# KX1_DB.net
KiCad netlist of a schematic drawn in Altium Designer
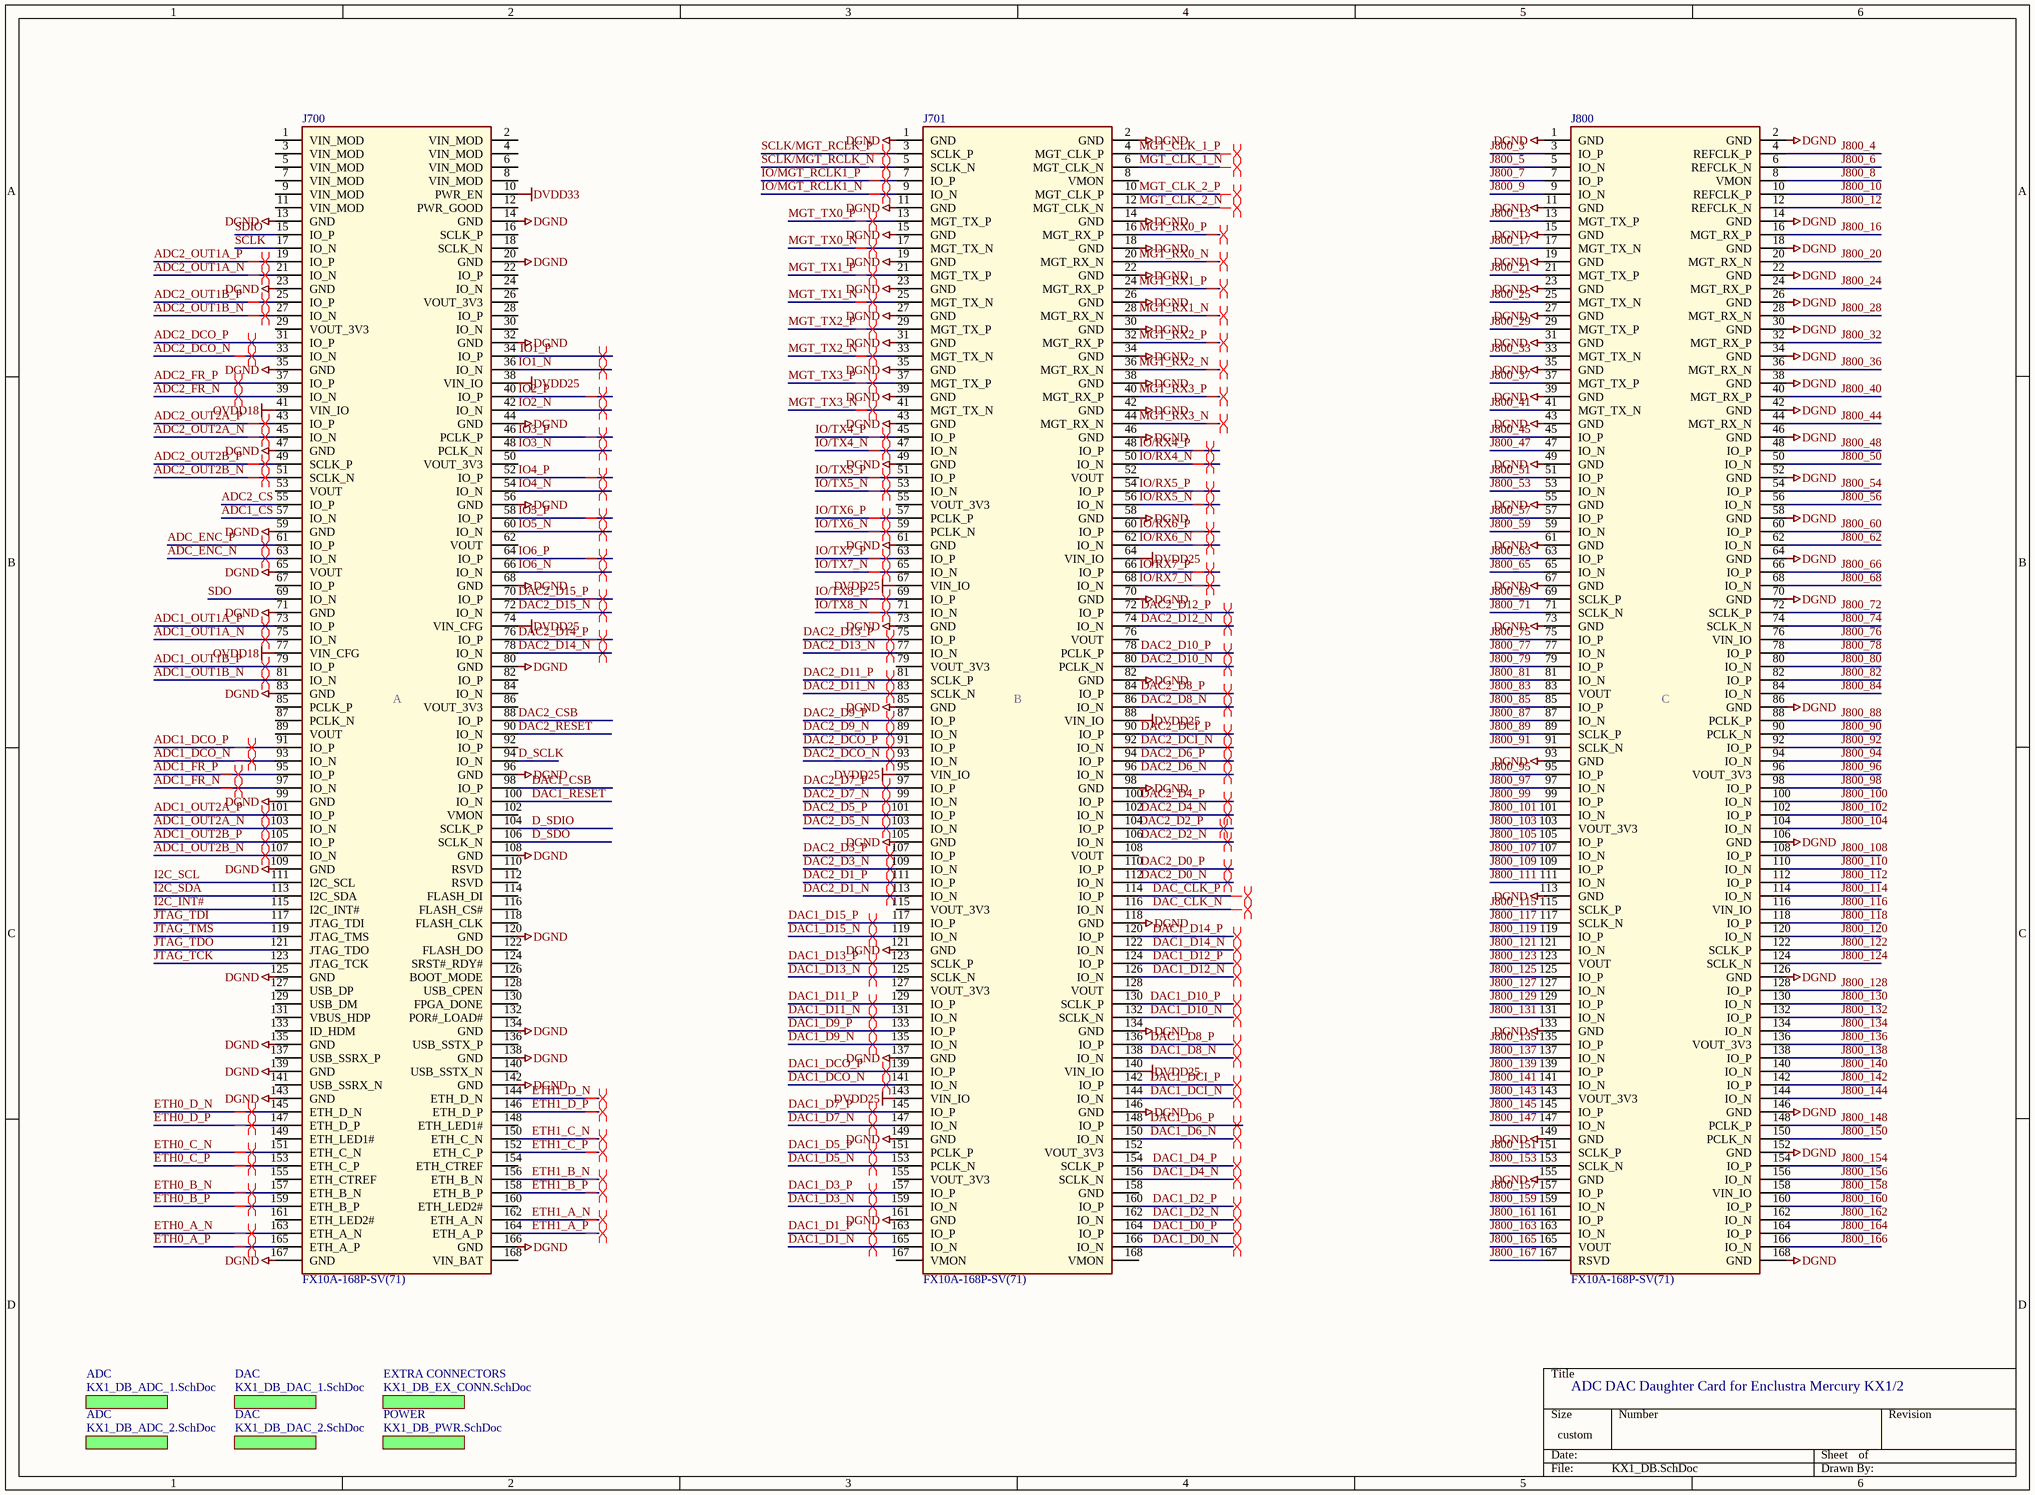
[diagram p0: KX1_DB.SchDoc]

(export (version "E")
  (design (tool "Eeschema 10.0.6"))
  (components
    (comp (ref "J700")
      (value "FX10A-168P-SV(71)")
      (footprint "Mercury_Baseboard_Connector")
      (description "Mercury Baseboard Connector")
      (fields
        (field (name "MANUFACTURER") "Hirose")
        (field (name "DISTPARTNUMBER") "FX10A-168P-SV(71)-ND")
        (field (name "CHECK SCH") "CG_2015-03-03")
      )
      (libsource (lib "Enclustra-Mars-Mercury-Altium-Library") (part "Mercury_Baseboard_Connector-A"))
    )
    (comp (ref "J701")
      (value "FX10A-168P-SV(71)")
      (footprint "Mercury_Baseboard_Connector")
      (description "Mercury Baseboard Connector")
      (fields
        (field (name "MANUFACTURER") "Hirose")
        (field (name "DISTPARTNUMBER") "FX10A-168P-SV(71)-ND")
        (field (name "CHECK SCH") "CG_2015-03-03")
      )
      (libsource (lib "Enclustra-Mars-Mercury-Altium-Library") (part "Mercury_Baseboard_Connector-B"))
    )
    (comp (ref "J800")
      (value "FX10A-168P-SV(71)")
      (footprint "Mercury_Baseboard_Connector")
      (description "Mercury Baseboard Connector")
      (fields
        (field (name "MANUFACTURER") "Hirose")
        (field (name "DISTPARTNUMBER") "FX10A-168P-SV(71)-ND")
        (field (name "CHECK SCH") "CG_2015-03-03")
      )
      (libsource (lib "Enclustra-Mars-Mercury-Altium-Library") (part "Mercury_Baseboard_Connector-C"))
    )
  )
  (nets
    (net (code "1") (name "/ADC1_CS") (class "Default")
      (node (ref "J700") (pin "57") (pinfunction "IO_N_57") (pintype "passive"))
    )
    (net (code "2") (name "/ADC1_DCO_N") (class "Default")
      (node (ref "J700") (pin "93") (pinfunction "IO_N_93") (pintype "passive"))
    )
    (net (code "3") (name "/ADC1_DCO_P") (class "Default")
      (node (ref "J700") (pin "91") (pinfunction "IO_P_91") (pintype "passive"))
    )
    (net (code "4") (name "/ADC1_FR_N") (class "Default")
      (node (ref "J700") (pin "97") (pinfunction "IO_N_97") (pintype "passive"))
    )
    (net (code "5") (name "/ADC1_FR_P") (class "Default")
      (node (ref "J700") (pin "95") (pinfunction "IO_P_95") (pintype "passive"))
    )
    (net (code "6") (name "/ADC1_OUT1A_N") (class "Default")
      (node (ref "J700") (pin "75") (pinfunction "IO_N_75") (pintype "passive"))
    )
    (net (code "7") (name "/ADC1_OUT1A_P") (class "Default")
      (node (ref "J700") (pin "73") (pinfunction "IO_P_73") (pintype "passive"))
    )
    (net (code "8") (name "/ADC1_OUT1B_N") (class "Default")
      (node (ref "J700") (pin "81") (pinfunction "IO_N_81") (pintype "passive"))
    )
    (net (code "9") (name "/ADC1_OUT1B_P") (class "Default")
      (node (ref "J700") (pin "79") (pinfunction "IO_P_79") (pintype "passive"))
    )
    (net (code "10") (name "/ADC1_OUT2A_N") (class "Default")
      (node (ref "J700") (pin "103") (pinfunction "IO_N_103") (pintype "passive"))
    )
    (net (code "11") (name "/ADC1_OUT2A_P") (class "Default")
      (node (ref "J700") (pin "101") (pinfunction "IO_P_101") (pintype "passive"))
    )
    (net (code "12") (name "/ADC1_OUT2B_N") (class "Default")
      (node (ref "J700") (pin "107") (pinfunction "IO_N_107") (pintype "passive"))
    )
    (net (code "13") (name "/ADC1_OUT2B_P") (class "Default")
      (node (ref "J700") (pin "105") (pinfunction "IO_P_105") (pintype "passive"))
    )
    (net (code "14") (name "/ADC2_CS") (class "Default")
      (node (ref "J700") (pin "55") (pinfunction "IO_P_55") (pintype "passive"))
    )
    (net (code "15") (name "/ADC2_DCO_N") (class "Default")
      (node (ref "J700") (pin "33") (pinfunction "IO_N_33") (pintype "passive"))
    )
    (net (code "16") (name "/ADC2_DCO_P") (class "Default")
      (node (ref "J700") (pin "31") (pinfunction "IO_P_31") (pintype "passive"))
    )
    (net (code "17") (name "/ADC2_FR_N") (class "Default")
      (node (ref "J700") (pin "39") (pinfunction "IO_N_39") (pintype "passive"))
    )
    (net (code "18") (name "/ADC2_FR_P") (class "Default")
      (node (ref "J700") (pin "37") (pinfunction "IO_P_37") (pintype "passive"))
    )
    (net (code "19") (name "/ADC2_OUT1A_N") (class "Default")
      (node (ref "J700") (pin "21") (pinfunction "IO_N_21") (pintype "passive"))
    )
    (net (code "20") (name "/ADC2_OUT1A_P") (class "Default")
      (node (ref "J700") (pin "19") (pinfunction "IO_P_19") (pintype "passive"))
    )
    (net (code "21") (name "/ADC2_OUT1B_N") (class "Default")
      (node (ref "J700") (pin "27") (pinfunction "IO_N_27") (pintype "passive"))
    )
    (net (code "22") (name "/ADC2_OUT1B_P") (class "Default")
      (node (ref "J700") (pin "25") (pinfunction "IO_P_25") (pintype "passive"))
    )
    (net (code "23") (name "/ADC2_OUT2A_N") (class "Default")
      (node (ref "J700") (pin "45") (pinfunction "IO_N_45") (pintype "passive"))
    )
    (net (code "24") (name "/ADC2_OUT2A_P") (class "Default")
      (node (ref "J700") (pin "43") (pinfunction "IO_P_43") (pintype "passive"))
    )
    (net (code "25") (name "/ADC2_OUT2B_N") (class "Default")
      (node (ref "J700") (pin "51") (pinfunction "SCLK_N_51") (pintype "passive"))
    )
    (net (code "26") (name "/ADC2_OUT2B_P") (class "Default")
      (node (ref "J700") (pin "49") (pinfunction "SCLK_P_49") (pintype "passive"))
    )
    (net (code "27") (name "/ADC_ENC_N") (class "Default")
      (node (ref "J700") (pin "63") (pinfunction "IO_N_63") (pintype "passive"))
    )
    (net (code "28") (name "/ADC_ENC_P") (class "Default")
      (node (ref "J700") (pin "61") (pinfunction "IO_P_61") (pintype "passive"))
    )
    (net (code "29") (name "/DAC1_CSB") (class "Default")
      (node (ref "J700") (pin "98") (pinfunction "IO_P_98") (pintype "passive"))
    )
    (net (code "30") (name "/DAC1_D0_N") (class "Default")
      (node (ref "J701") (pin "166") (pinfunction "IO_N_166") (pintype "passive"))
    )
    (net (code "31") (name "/DAC1_D0_P") (class "Default")
      (node (ref "J701") (pin "164") (pinfunction "IO_P_164") (pintype "passive"))
    )
    (net (code "32") (name "/DAC1_D1_N") (class "Default")
      (node (ref "J701") (pin "165") (pinfunction "IO_N_165") (pintype "passive"))
    )
    (net (code "33") (name "/DAC1_D1_P") (class "Default")
      (node (ref "J701") (pin "163") (pinfunction "IO_P_163") (pintype "passive"))
    )
    (net (code "34") (name "/DAC1_D2_N") (class "Default")
      (node (ref "J701") (pin "162") (pinfunction "IO_N_162") (pintype "passive"))
    )
    (net (code "35") (name "/DAC1_D2_P") (class "Default")
      (node (ref "J701") (pin "160") (pinfunction "IO_P_160") (pintype "passive"))
    )
    (net (code "36") (name "/DAC1_D3_N") (class "Default")
      (node (ref "J701") (pin "159") (pinfunction "IO_N_159") (pintype "passive"))
    )
    (net (code "37") (name "/DAC1_D3_P") (class "Default")
      (node (ref "J701") (pin "157") (pinfunction "IO_P_157") (pintype "passive"))
    )
    (net (code "38") (name "/DAC1_D4_N") (class "Default")
      (node (ref "J701") (pin "156") (pinfunction "SCLK_N_156") (pintype "passive"))
    )
    (net (code "39") (name "/DAC1_D4_P") (class "Default")
      (node (ref "J701") (pin "154") (pinfunction "SCLK_P_154") (pintype "passive"))
    )
    (net (code "40") (name "/DAC1_D5_N") (class "Default")
      (node (ref "J701") (pin "153") (pinfunction "PCLK_N_153") (pintype "passive"))
    )
    (net (code "41") (name "/DAC1_D5_P") (class "Default")
      (node (ref "J701") (pin "151") (pinfunction "PCLK_P_151") (pintype "passive"))
    )
    (net (code "42") (name "/DAC1_D6_N") (class "Default")
      (node (ref "J701") (pin "150") (pinfunction "IO_N_150") (pintype "passive"))
    )
    (net (code "43") (name "/DAC1_D6_P") (class "Default")
      (node (ref "J701") (pin "148") (pinfunction "IO_P_148") (pintype "passive"))
    )
    (net (code "44") (name "/DAC1_D7_N") (class "Default")
      (node (ref "J701") (pin "147") (pinfunction "IO_N_147") (pintype "passive"))
    )
    (net (code "45") (name "/DAC1_D7_P") (class "Default")
      (node (ref "J701") (pin "145") (pinfunction "IO_P_145") (pintype "passive"))
    )
    (net (code "46") (name "/DAC1_D8_N") (class "Default")
      (node (ref "J701") (pin "138") (pinfunction "IO_N_138") (pintype "passive"))
    )
    (net (code "47") (name "/DAC1_D8_P") (class "Default")
      (node (ref "J701") (pin "136") (pinfunction "IO_P_136") (pintype "passive"))
    )
    (net (code "48") (name "/DAC1_D9_N") (class "Default")
      (node (ref "J701") (pin "135") (pinfunction "IO_N_135") (pintype "passive"))
    )
    (net (code "49") (name "/DAC1_D9_P") (class "Default")
      (node (ref "J701") (pin "133") (pinfunction "IO_P_133") (pintype "passive"))
    )
    (net (code "50") (name "/DAC1_D10_N") (class "Default")
      (node (ref "J701") (pin "132") (pinfunction "SCLK_N_132") (pintype "passive"))
    )
    (net (code "51") (name "/DAC1_D10_P") (class "Default")
      (node (ref "J701") (pin "130") (pinfunction "SCLK_P_130") (pintype "passive"))
    )
    (net (code "52") (name "/DAC1_D11_N") (class "Default")
      (node (ref "J701") (pin "131") (pinfunction "IO_N_131") (pintype "passive"))
    )
    (net (code "53") (name "/DAC1_D11_P") (class "Default")
      (node (ref "J701") (pin "129") (pinfunction "IO_P_129") (pintype "passive"))
    )
    (net (code "54") (name "/DAC1_D12_N") (class "Default")
      (node (ref "J701") (pin "126") (pinfunction "IO_N_126") (pintype "passive"))
    )
    (net (code "55") (name "/DAC1_D12_P") (class "Default")
      (node (ref "J701") (pin "124") (pinfunction "IO_P_124") (pintype "passive"))
    )
    (net (code "56") (name "/DAC1_D13_N") (class "Default")
      (node (ref "J701") (pin "125") (pinfunction "SCLK_N_125") (pintype "passive"))
    )
    (net (code "57") (name "/DAC1_D13_P") (class "Default")
      (node (ref "J701") (pin "123") (pinfunction "SCLK_P_123") (pintype "passive"))
    )
    (net (code "58") (name "/DAC1_D14_N") (class "Default")
      (node (ref "J701") (pin "122") (pinfunction "IO_N_122") (pintype "passive"))
    )
    (net (code "59") (name "/DAC1_D14_P") (class "Default")
      (node (ref "J701") (pin "120") (pinfunction "IO_P_120") (pintype "passive"))
    )
    (net (code "60") (name "/DAC1_D15_N") (class "Default")
      (node (ref "J701") (pin "119") (pinfunction "IO_N_119") (pintype "passive"))
    )
    (net (code "61") (name "/DAC1_D15_P") (class "Default")
      (node (ref "J701") (pin "117") (pinfunction "IO_P_117") (pintype "passive"))
    )
    (net (code "62") (name "/DAC1_DCI_N") (class "Default")
      (node (ref "J701") (pin "144") (pinfunction "IO_N_144") (pintype "passive"))
    )
    (net (code "63") (name "/DAC1_DCI_P") (class "Default")
      (node (ref "J701") (pin "142") (pinfunction "IO_P_142") (pintype "passive"))
    )
    (net (code "64") (name "/DAC1_DCO_N") (class "Default")
      (node (ref "J701") (pin "141") (pinfunction "IO_N_141") (pintype "passive"))
    )
    (net (code "65") (name "/DAC1_DCO_P") (class "Default")
      (node (ref "J701") (pin "139") (pinfunction "IO_P_139") (pintype "passive"))
    )
    (net (code "66") (name "/DAC1_RESET") (class "Default")
      (node (ref "J700") (pin "100") (pinfunction "IO_N_100") (pintype "passive"))
    )
    (net (code "67") (name "/DAC2_CSB") (class "Default")
      (node (ref "J700") (pin "88") (pinfunction "IO_P_88") (pintype "passive"))
    )
    (net (code "68") (name "/DAC2_D0_N") (class "Default")
      (node (ref "J701") (pin "112") (pinfunction "IO_N_112") (pintype "passive"))
    )
    (net (code "69") (name "/DAC2_D0_P") (class "Default")
      (node (ref "J701") (pin "110") (pinfunction "IO_P_110") (pintype "passive"))
    )
    (net (code "70") (name "/DAC2_D1_N") (class "Default")
      (node (ref "J701") (pin "113") (pinfunction "IO_N_113") (pintype "passive"))
    )
    (net (code "71") (name "/DAC2_D1_P") (class "Default")
      (node (ref "J701") (pin "111") (pinfunction "IO_P_111") (pintype "passive"))
    )
    (net (code "72") (name "/DAC2_D2_N") (class "Default")
      (node (ref "J701") (pin "106") (pinfunction "IO_N_106") (pintype "passive"))
    )
    (net (code "73") (name "/DAC2_D2_P") (class "Default")
      (node (ref "J701") (pin "104") (pinfunction "IO_P_104") (pintype "passive"))
    )
    (net (code "74") (name "/DAC2_D3_N") (class "Default")
      (node (ref "J701") (pin "109") (pinfunction "IO_N_109") (pintype "passive"))
    )
    (net (code "75") (name "/DAC2_D3_P") (class "Default")
      (node (ref "J701") (pin "107") (pinfunction "IO_P_107") (pintype "passive"))
    )
    (net (code "76") (name "/DAC2_D4_N") (class "Default")
      (node (ref "J701") (pin "102") (pinfunction "IO_N_102") (pintype "passive"))
    )
    (net (code "77") (name "/DAC2_D4_P") (class "Default")
      (node (ref "J701") (pin "100") (pinfunction "IO_P_100") (pintype "passive"))
    )
    (net (code "78") (name "/DAC2_D5_N") (class "Default")
      (node (ref "J701") (pin "103") (pinfunction "IO_N_103") (pintype "passive"))
    )
    (net (code "79") (name "/DAC2_D5_P") (class "Default")
      (node (ref "J701") (pin "101") (pinfunction "IO_P_101") (pintype "passive"))
    )
    (net (code "80") (name "/DAC2_D6_N") (class "Default")
      (node (ref "J701") (pin "96") (pinfunction "IO_N_96") (pintype "passive"))
    )
    (net (code "81") (name "/DAC2_D6_P") (class "Default")
      (node (ref "J701") (pin "94") (pinfunction "IO_P_94") (pintype "passive"))
    )
    (net (code "82") (name "/DAC2_D7_N") (class "Default")
      (node (ref "J701") (pin "99") (pinfunction "IO_N_99") (pintype "passive"))
    )
    (net (code "83") (name "/DAC2_D7_P") (class "Default")
      (node (ref "J701") (pin "97") (pinfunction "IO_P_97") (pintype "passive"))
    )
    (net (code "84") (name "/DAC2_D8_N") (class "Default")
      (node (ref "J701") (pin "86") (pinfunction "IO_N_86") (pintype "passive"))
    )
    (net (code "85") (name "/DAC2_D8_P") (class "Default")
      (node (ref "J701") (pin "84") (pinfunction "IO_P_84") (pintype "passive"))
    )
    (net (code "86") (name "/DAC2_D9_N") (class "Default")
      (node (ref "J701") (pin "89") (pinfunction "IO_N_89") (pintype "passive"))
    )
    (net (code "87") (name "/DAC2_D9_P") (class "Default")
      (node (ref "J701") (pin "87") (pinfunction "IO_P_87") (pintype "passive"))
    )
    (net (code "88") (name "/DAC2_D10_N") (class "Default")
      (node (ref "J701") (pin "80") (pinfunction "PCLK_N_80") (pintype "passive"))
    )
    (net (code "89") (name "/DAC2_D10_P") (class "Default")
      (node (ref "J701") (pin "78") (pinfunction "PCLK_P_78") (pintype "passive"))
    )
    (net (code "90") (name "/DAC2_D11_N") (class "Default")
      (node (ref "J701") (pin "83") (pinfunction "SCLK_N_83") (pintype "passive"))
    )
    (net (code "91") (name "/DAC2_D11_P") (class "Default")
      (node (ref "J701") (pin "81") (pinfunction "SCLK_P_81") (pintype "passive"))
    )
    (net (code "92") (name "/DAC2_D12_N") (class "Default")
      (node (ref "J701") (pin "74") (pinfunction "IO_N_74") (pintype "passive"))
    )
    (net (code "93") (name "/DAC2_D12_P") (class "Default")
      (node (ref "J701") (pin "72") (pinfunction "IO_P_72") (pintype "passive"))
    )
    (net (code "94") (name "/DAC2_D13_N") (class "Default")
      (node (ref "J701") (pin "77") (pinfunction "IO_N_77") (pintype "passive"))
    )
    (net (code "95") (name "/DAC2_D13_P") (class "Default")
      (node (ref "J701") (pin "75") (pinfunction "IO_P_75") (pintype "passive"))
    )
    (net (code "96") (name "/DAC2_D14_N") (class "Default")
      (node (ref "J700") (pin "78") (pinfunction "IO_N_78") (pintype "passive"))
    )
    (net (code "97") (name "/DAC2_D14_P") (class "Default")
      (node (ref "J700") (pin "76") (pinfunction "IO_P_76") (pintype "passive"))
    )
    (net (code "98") (name "/DAC2_D15_N") (class "Default")
      (node (ref "J700") (pin "72") (pinfunction "IO_N_72") (pintype "passive"))
    )
    (net (code "99") (name "/DAC2_D15_P") (class "Default")
      (node (ref "J700") (pin "70") (pinfunction "IO_P_70") (pintype "passive"))
    )
    (net (code "100") (name "/DAC2_DCI_N") (class "Default")
      (node (ref "J701") (pin "92") (pinfunction "IO_N_92") (pintype "passive"))
    )
    (net (code "101") (name "/DAC2_DCI_P") (class "Default")
      (node (ref "J701") (pin "90") (pinfunction "IO_P_90") (pintype "passive"))
    )
    (net (code "102") (name "/DAC2_DCO_N") (class "Default")
      (node (ref "J701") (pin "93") (pinfunction "IO_N_93") (pintype "passive"))
    )
    (net (code "103") (name "/DAC2_DCO_P") (class "Default")
      (node (ref "J701") (pin "91") (pinfunction "IO_P_91") (pintype "passive"))
    )
    (net (code "104") (name "/DAC2_RESET") (class "Default")
      (node (ref "J700") (pin "90") (pinfunction "IO_N_90") (pintype "passive"))
    )
    (net (code "105") (name "/DAC_CLK_N") (class "Default")
      (node (ref "J701") (pin "116") (pinfunction "IO_N_116") (pintype "passive"))
    )
    (net (code "106") (name "/DAC_CLK_P") (class "Default")
      (node (ref "J701") (pin "114") (pinfunction "IO_P_114") (pintype "passive"))
    )
    (net (code "107") (name "/D_SCLK") (class "Default")
      (node (ref "J700") (pin "94") (pinfunction "IO_N_94") (pintype "passive"))
    )
    (net (code "108") (name "/D_SDIO") (class "Default")
      (node (ref "J700") (pin "104") (pinfunction "SCLK_P_104") (pintype "passive"))
    )
    (net (code "109") (name "/D_SDO") (class "Default")
      (node (ref "J700") (pin "106") (pinfunction "SCLK_N_106") (pintype "passive"))
    )
    (net (code "110") (name "/ETH0_A_N") (class "Default")
      (node (ref "J700") (pin "163") (pinfunction "ETH_A_N_163") (pintype "passive"))
    )
    (net (code "111") (name "/ETH0_A_P") (class "Default")
      (node (ref "J700") (pin "165") (pinfunction "ETH_A_P_165") (pintype "passive"))
    )
    (net (code "112") (name "/ETH0_B_N") (class "Default")
      (node (ref "J700") (pin "157") (pinfunction "ETH_B_N_157") (pintype "passive"))
    )
    (net (code "113") (name "/ETH0_B_P") (class "Default")
      (node (ref "J700") (pin "159") (pinfunction "ETH_B_P_159") (pintype "passive"))
    )
    (net (code "114") (name "/ETH0_C_N") (class "Default")
      (node (ref "J700") (pin "151") (pinfunction "ETH_C_N_151") (pintype "passive"))
    )
    (net (code "115") (name "/ETH0_C_P") (class "Default")
      (node (ref "J700") (pin "153") (pinfunction "ETH_C_P_153") (pintype "passive"))
    )
    (net (code "116") (name "/ETH0_D_N") (class "Default")
      (node (ref "J700") (pin "145") (pinfunction "ETH_D_N_145") (pintype "passive"))
    )
    (net (code "117") (name "/ETH0_D_P") (class "Default")
      (node (ref "J700") (pin "147") (pinfunction "ETH_D_P_147") (pintype "passive"))
    )
    (net (code "118") (name "/ETH1_A_N") (class "Default")
      (node (ref "J700") (pin "162") (pinfunction "ETH_A_N_162") (pintype "passive"))
    )
    (net (code "119") (name "/ETH1_A_P") (class "Default")
      (node (ref "J700") (pin "164") (pinfunction "ETH_A_P_164") (pintype "passive"))
    )
    (net (code "120") (name "/ETH1_B_N") (class "Default")
      (node (ref "J700") (pin "156") (pinfunction "ETH_B_N_156") (pintype "passive"))
    )
    (net (code "121") (name "/ETH1_B_P") (class "Default")
      (node (ref "J700") (pin "158") (pinfunction "ETH_B_P_158") (pintype "passive"))
    )
    (net (code "122") (name "/ETH1_C_N") (class "Default")
      (node (ref "J700") (pin "150") (pinfunction "ETH_C_N_150") (pintype "passive"))
    )
    (net (code "123") (name "/ETH1_C_P") (class "Default")
      (node (ref "J700") (pin "152") (pinfunction "ETH_C_P_152") (pintype "passive"))
    )
    (net (code "124") (name "/ETH1_D_N") (class "Default")
      (node (ref "J700") (pin "144") (pinfunction "ETH_D_N_144") (pintype "passive"))
    )
    (net (code "125") (name "/ETH1_D_P") (class "Default")
      (node (ref "J700") (pin "146") (pinfunction "ETH_D_P_146") (pintype "passive"))
    )
    (net (code "126") (name "/I2C_INT#") (class "Default")
      (node (ref "J700") (pin "115") (pinfunction "I2C_INT#_115") (pintype "passive"))
    )
    (net (code "127") (name "/I2C_SCL") (class "Default")
      (node (ref "J700") (pin "111") (pinfunction "I2C_SCL_111") (pintype "passive"))
    )
    (net (code "128") (name "/I2C_SDA") (class "Default")
      (node (ref "J700") (pin "113") (pinfunction "I2C_SDA_113") (pintype "passive"))
    )
    (net (code "129") (name "/IO1_N") (class "Default")
      (node (ref "J700") (pin "36") (pinfunction "IO_N_36") (pintype "passive"))
    )
    (net (code "130") (name "/IO1_P") (class "Default")
      (node (ref "J700") (pin "34") (pinfunction "IO_P_34") (pintype "passive"))
    )
    (net (code "131") (name "/IO2_N") (class "Default")
      (node (ref "J700") (pin "42") (pinfunction "IO_N_42") (pintype "passive"))
    )
    (net (code "132") (name "/IO2_P") (class "Default")
      (node (ref "J700") (pin "40") (pinfunction "IO_P_40") (pintype "passive"))
    )
    (net (code "133") (name "/IO3_N") (class "Default")
      (node (ref "J700") (pin "48") (pinfunction "PCLK_N_48") (pintype "passive"))
    )
    (net (code "134") (name "/IO3_P") (class "Default")
      (node (ref "J700") (pin "46") (pinfunction "PCLK_P_46") (pintype "passive"))
    )
    (net (code "135") (name "/IO4_N") (class "Default")
      (node (ref "J700") (pin "54") (pinfunction "IO_N_54") (pintype "passive"))
    )
    (net (code "136") (name "/IO4_P") (class "Default")
      (node (ref "J700") (pin "52") (pinfunction "IO_P_52") (pintype "passive"))
    )
    (net (code "137") (name "/IO5_N") (class "Default")
      (node (ref "J700") (pin "60") (pinfunction "IO_N_60") (pintype "passive"))
    )
    (net (code "138") (name "/IO5_P") (class "Default")
      (node (ref "J700") (pin "58") (pinfunction "IO_P_58") (pintype "passive"))
    )
    (net (code "139") (name "/IO6_N") (class "Default")
      (node (ref "J700") (pin "66") (pinfunction "IO_N_66") (pintype "passive"))
    )
    (net (code "140") (name "/IO6_P") (class "Default")
      (node (ref "J700") (pin "64") (pinfunction "IO_P_64") (pintype "passive"))
    )
    (net (code "141") (name "/IO{slash}MGT_RCLK1_N") (class "Default")
      (node (ref "J701") (pin "9") (pinfunction "IO_N_9") (pintype "passive"))
    )
    (net (code "142") (name "/IO{slash}MGT_RCLK1_P") (class "Default")
      (node (ref "J701") (pin "7") (pinfunction "IO_P_7") (pintype "passive"))
    )
    (net (code "143") (name "/IO{slash}RX4_N") (class "Default")
      (node (ref "J701") (pin "50") (pinfunction "IO_N_50") (pintype "passive"))
    )
    (net (code "144") (name "/IO{slash}RX4_P") (class "Default")
      (node (ref "J701") (pin "48") (pinfunction "IO_P_48") (pintype "passive"))
    )
    (net (code "145") (name "/IO{slash}RX5_N") (class "Default")
      (node (ref "J701") (pin "56") (pinfunction "IO_N_56") (pintype "passive"))
    )
    (net (code "146") (name "/IO{slash}RX5_P") (class "Default")
      (node (ref "J701") (pin "54") (pinfunction "IO_P_54") (pintype "passive"))
    )
    (net (code "147") (name "/IO{slash}RX6_N") (class "Default")
      (node (ref "J701") (pin "62") (pinfunction "IO_N_62") (pintype "passive"))
    )
    (net (code "148") (name "/IO{slash}RX6_P") (class "Default")
      (node (ref "J701") (pin "60") (pinfunction "IO_P_60") (pintype "passive"))
    )
    (net (code "149") (name "/IO{slash}RX7_N") (class "Default")
      (node (ref "J701") (pin "68") (pinfunction "IO_N_68") (pintype "passive"))
    )
    (net (code "150") (name "/IO{slash}RX7_P") (class "Default")
      (node (ref "J701") (pin "66") (pinfunction "IO_P_66") (pintype "passive"))
    )
    (net (code "151") (name "/IO{slash}TX4_N") (class "Default")
      (node (ref "J701") (pin "47") (pinfunction "IO_N_47") (pintype "passive"))
    )
    (net (code "152") (name "/IO{slash}TX4_P") (class "Default")
      (node (ref "J701") (pin "45") (pinfunction "IO_P_45") (pintype "passive"))
    )
    (net (code "153") (name "/IO{slash}TX5_N") (class "Default")
      (node (ref "J701") (pin "53") (pinfunction "IO_N_53") (pintype "passive"))
    )
    (net (code "154") (name "/IO{slash}TX5_P") (class "Default")
      (node (ref "J701") (pin "51") (pinfunction "IO_P_51") (pintype "passive"))
    )
    (net (code "155") (name "/IO{slash}TX6_N") (class "Default")
      (node (ref "J701") (pin "59") (pinfunction "PCLK_N_59") (pintype "passive"))
    )
    (net (code "156") (name "/IO{slash}TX6_P") (class "Default")
      (node (ref "J701") (pin "57") (pinfunction "PCLK_P_57") (pintype "passive"))
    )
    (net (code "157") (name "/IO{slash}TX7_N") (class "Default")
      (node (ref "J701") (pin "65") (pinfunction "IO_N_65") (pintype "passive"))
    )
    (net (code "158") (name "/IO{slash}TX7_P") (class "Default")
      (node (ref "J701") (pin "63") (pinfunction "IO_P_63") (pintype "passive"))
    )
    (net (code "159") (name "/IO{slash}TX8_N") (class "Default")
      (node (ref "J701") (pin "71") (pinfunction "IO_N_71") (pintype "passive"))
    )
    (net (code "160") (name "/IO{slash}TX8_P") (class "Default")
      (node (ref "J701") (pin "69") (pinfunction "IO_P_69") (pintype "passive"))
    )
    (net (code "161") (name "/J800_3") (class "Default")
      (node (ref "J800") (pin "3") (pinfunction "IO_P_3") (pintype "passive"))
    )
    (net (code "162") (name "/J800_4") (class "Default")
      (node (ref "J800") (pin "4") (pinfunction "REFCLK_P_4") (pintype "passive"))
    )
    (net (code "163") (name "/J800_5") (class "Default")
      (node (ref "J800") (pin "5") (pinfunction "IO_N_5") (pintype "passive"))
    )
    (net (code "164") (name "/J800_6") (class "Default")
      (node (ref "J800") (pin "6") (pinfunction "REFCLK_N_6") (pintype "passive"))
    )
    (net (code "165") (name "/J800_7") (class "Default")
      (node (ref "J800") (pin "7") (pinfunction "IO_P_7") (pintype "passive"))
    )
    (net (code "166") (name "/J800_8") (class "Default")
      (node (ref "J800") (pin "8") (pinfunction "VMON_8") (pintype "passive"))
    )
    (net (code "167") (name "/J800_9") (class "Default")
      (node (ref "J800") (pin "9") (pinfunction "IO_N_9") (pintype "passive"))
    )
    (net (code "168") (name "/J800_10") (class "Default")
      (node (ref "J800") (pin "10") (pinfunction "REFCLK_P_10") (pintype "passive"))
    )
    (net (code "169") (name "/J800_12") (class "Default")
      (node (ref "J800") (pin "12") (pinfunction "REFCLK_N_12") (pintype "passive"))
    )
    (net (code "170") (name "/J800_13") (class "Default")
      (node (ref "J800") (pin "13") (pinfunction "MGT_TX_P_13") (pintype "passive"))
    )
    (net (code "171") (name "/J800_16") (class "Default")
      (node (ref "J800") (pin "16") (pinfunction "MGT_RX_P_16") (pintype "passive"))
    )
    (net (code "172") (name "/J800_17") (class "Default")
      (node (ref "J800") (pin "17") (pinfunction "MGT_TX_N_17") (pintype "passive"))
    )
    (net (code "173") (name "/J800_20") (class "Default")
      (node (ref "J800") (pin "20") (pinfunction "MGT_RX_N_20") (pintype "passive"))
    )
    (net (code "174") (name "/J800_21") (class "Default")
      (node (ref "J800") (pin "21") (pinfunction "MGT_TX_P_21") (pintype "passive"))
    )
    (net (code "175") (name "/J800_24") (class "Default")
      (node (ref "J800") (pin "24") (pinfunction "MGT_RX_P_24") (pintype "passive"))
    )
    (net (code "176") (name "/J800_25") (class "Default")
      (node (ref "J800") (pin "25") (pinfunction "MGT_TX_N_25") (pintype "passive"))
    )
    (net (code "177") (name "/J800_28") (class "Default")
      (node (ref "J800") (pin "28") (pinfunction "MGT_RX_N_28") (pintype "passive"))
    )
    (net (code "178") (name "/J800_29") (class "Default")
      (node (ref "J800") (pin "29") (pinfunction "MGT_TX_P_29") (pintype "passive"))
    )
    (net (code "179") (name "/J800_32") (class "Default")
      (node (ref "J800") (pin "32") (pinfunction "MGT_RX_P_32") (pintype "passive"))
    )
    (net (code "180") (name "/J800_33") (class "Default")
      (node (ref "J800") (pin "33") (pinfunction "MGT_TX_N_33") (pintype "passive"))
    )
    (net (code "181") (name "/J800_36") (class "Default")
      (node (ref "J800") (pin "36") (pinfunction "MGT_RX_N_36") (pintype "passive"))
    )
    (net (code "182") (name "/J800_37") (class "Default")
      (node (ref "J800") (pin "37") (pinfunction "MGT_TX_P_37") (pintype "passive"))
    )
    (net (code "183") (name "/J800_40") (class "Default")
      (node (ref "J800") (pin "40") (pinfunction "MGT_RX_P_40") (pintype "passive"))
    )
    (net (code "184") (name "/J800_41") (class "Default")
      (node (ref "J800") (pin "41") (pinfunction "MGT_TX_N_41") (pintype "passive"))
    )
    (net (code "185") (name "/J800_44") (class "Default")
      (node (ref "J800") (pin "44") (pinfunction "MGT_RX_N_44") (pintype "passive"))
    )
    (net (code "186") (name "/J800_45") (class "Default")
      (node (ref "J800") (pin "45") (pinfunction "IO_P_45") (pintype "passive"))
    )
    (net (code "187") (name "/J800_47") (class "Default")
      (node (ref "J800") (pin "47") (pinfunction "IO_N_47") (pintype "passive"))
    )
    (net (code "188") (name "/J800_48") (class "Default")
      (node (ref "J800") (pin "48") (pinfunction "IO_P_48") (pintype "passive"))
    )
    (net (code "189") (name "/J800_50") (class "Default")
      (node (ref "J800") (pin "50") (pinfunction "IO_N_50") (pintype "passive"))
    )
    (net (code "190") (name "/J800_51") (class "Default")
      (node (ref "J800") (pin "51") (pinfunction "IO_P_51") (pintype "passive"))
    )
    (net (code "191") (name "/J800_53") (class "Default")
      (node (ref "J800") (pin "53") (pinfunction "IO_N_53") (pintype "passive"))
    )
    (net (code "192") (name "/J800_54") (class "Default")
      (node (ref "J800") (pin "54") (pinfunction "IO_P_54") (pintype "passive"))
    )
    (net (code "193") (name "/J800_56") (class "Default")
      (node (ref "J800") (pin "56") (pinfunction "IO_N_56") (pintype "passive"))
    )
    (net (code "194") (name "/J800_57") (class "Default")
      (node (ref "J800") (pin "57") (pinfunction "IO_P_57") (pintype "passive"))
    )
    (net (code "195") (name "/J800_59") (class "Default")
      (node (ref "J800") (pin "59") (pinfunction "IO_N_59") (pintype "passive"))
    )
    (net (code "196") (name "/J800_60") (class "Default")
      (node (ref "J800") (pin "60") (pinfunction "IO_P_60") (pintype "passive"))
    )
    (net (code "197") (name "/J800_62") (class "Default")
      (node (ref "J800") (pin "62") (pinfunction "IO_N_62") (pintype "passive"))
    )
    (net (code "198") (name "/J800_63") (class "Default")
      (node (ref "J800") (pin "63") (pinfunction "IO_P_63") (pintype "passive"))
    )
    (net (code "199") (name "/J800_65") (class "Default")
      (node (ref "J800") (pin "65") (pinfunction "IO_N_65") (pintype "passive"))
    )
    (net (code "200") (name "/J800_66") (class "Default")
      (node (ref "J800") (pin "66") (pinfunction "IO_P_66") (pintype "passive"))
    )
    (net (code "201") (name "/J800_68") (class "Default")
      (node (ref "J800") (pin "68") (pinfunction "IO_N_68") (pintype "passive"))
    )
    (net (code "202") (name "/J800_69") (class "Default")
      (node (ref "J800") (pin "69") (pinfunction "SCLK_P_69") (pintype "passive"))
    )
    (net (code "203") (name "/J800_71") (class "Default")
      (node (ref "J800") (pin "71") (pinfunction "SCLK_N_71") (pintype "passive"))
    )
    (net (code "204") (name "/J800_72") (class "Default")
      (node (ref "J800") (pin "72") (pinfunction "SCLK_P_72") (pintype "passive"))
    )
    (net (code "205") (name "/J800_74") (class "Default")
      (node (ref "J800") (pin "74") (pinfunction "SCLK_N_74") (pintype "passive"))
    )
    (net (code "206") (name "/J800_75") (class "Default")
      (node (ref "J800") (pin "75") (pinfunction "IO_P_75") (pintype "passive"))
    )
    (net (code "207") (name "/J800_76") (class "Default")
      (node (ref "J800") (pin "76") (pinfunction "VIN_IO_76") (pintype "passive"))
    )
    (net (code "208") (name "/J800_77") (class "Default")
      (node (ref "J800") (pin "77") (pinfunction "IO_N_77") (pintype "passive"))
    )
    (net (code "209") (name "/J800_78") (class "Default")
      (node (ref "J800") (pin "78") (pinfunction "IO_P_78") (pintype "passive"))
    )
    (net (code "210") (name "/J800_79") (class "Default")
      (node (ref "J800") (pin "79") (pinfunction "IO_P_79") (pintype "passive"))
    )
    (net (code "211") (name "/J800_80") (class "Default")
      (node (ref "J800") (pin "80") (pinfunction "IO_N_80") (pintype "passive"))
    )
    (net (code "212") (name "/J800_81") (class "Default")
      (node (ref "J800") (pin "81") (pinfunction "IO_N_81") (pintype "passive"))
    )
    (net (code "213") (name "/J800_82") (class "Default")
      (node (ref "J800") (pin "82") (pinfunction "IO_P_82") (pintype "passive"))
    )
    (net (code "214") (name "/J800_83") (class "Default")
      (node (ref "J800") (pin "83") (pinfunction "VOUT_83") (pintype "passive"))
    )
    (net (code "215") (name "/J800_84") (class "Default")
      (node (ref "J800") (pin "84") (pinfunction "IO_N_84") (pintype "passive"))
    )
    (net (code "216") (name "/J800_85") (class "Default")
      (node (ref "J800") (pin "85") (pinfunction "IO_P_85") (pintype "passive"))
    )
    (net (code "217") (name "/J800_87") (class "Default")
      (node (ref "J800") (pin "87") (pinfunction "IO_N_87") (pintype "passive"))
    )
    (net (code "218") (name "/J800_88") (class "Default")
      (node (ref "J800") (pin "88") (pinfunction "PCLK_P_88") (pintype "passive"))
    )
    (net (code "219") (name "/J800_89") (class "Default")
      (node (ref "J800") (pin "89") (pinfunction "SCLK_P_89") (pintype "passive"))
    )
    (net (code "220") (name "/J800_90") (class "Default")
      (node (ref "J800") (pin "90") (pinfunction "PCLK_N_90") (pintype "passive"))
    )
    (net (code "221") (name "/J800_91") (class "Default")
      (node (ref "J800") (pin "91") (pinfunction "SCLK_N_91") (pintype "passive"))
    )
    (net (code "222") (name "/J800_92") (class "Default")
      (node (ref "J800") (pin "92") (pinfunction "IO_P_92") (pintype "passive"))
    )
    (net (code "223") (name "/J800_94") (class "Default")
      (node (ref "J800") (pin "94") (pinfunction "IO_N_94") (pintype "passive"))
    )
    (net (code "224") (name "/J800_95") (class "Default")
      (node (ref "J800") (pin "95") (pinfunction "IO_P_95") (pintype "passive"))
    )
    (net (code "225") (name "/J800_96") (class "Default")
      (node (ref "J800") (pin "96") (pinfunction "VOUT_3V3_96") (pintype "passive"))
    )
    (net (code "226") (name "/J800_97") (class "Default")
      (node (ref "J800") (pin "97") (pinfunction "IO_N_97") (pintype "passive"))
    )
    (net (code "227") (name "/J800_98") (class "Default")
      (node (ref "J800") (pin "98") (pinfunction "IO_P_98") (pintype "passive"))
    )
    (net (code "228") (name "/J800_99") (class "Default")
      (node (ref "J800") (pin "99") (pinfunction "IO_P_99") (pintype "passive"))
    )
    (net (code "229") (name "/J800_100") (class "Default")
      (node (ref "J800") (pin "100") (pinfunction "IO_N_100") (pintype "passive"))
    )
    (net (code "230") (name "/J800_101") (class "Default")
      (node (ref "J800") (pin "101") (pinfunction "IO_N_101") (pintype "passive"))
    )
    (net (code "231") (name "/J800_102") (class "Default")
      (node (ref "J800") (pin "102") (pinfunction "IO_P_102") (pintype "passive"))
    )
    (net (code "232") (name "/J800_103") (class "Default")
      (node (ref "J800") (pin "103") (pinfunction "VOUT_3V3_103") (pintype "passive"))
    )
    (net (code "233") (name "/J800_104") (class "Default")
      (node (ref "J800") (pin "104") (pinfunction "IO_N_104") (pintype "passive"))
    )
    (net (code "234") (name "/J800_105") (class "Default")
      (node (ref "J800") (pin "105") (pinfunction "IO_P_105") (pintype "passive"))
    )
    (net (code "235") (name "/J800_107") (class "Default")
      (node (ref "J800") (pin "107") (pinfunction "IO_N_107") (pintype "passive"))
    )
    (net (code "236") (name "/J800_108") (class "Default")
      (node (ref "J800") (pin "108") (pinfunction "IO_P_108") (pintype "passive"))
    )
    (net (code "237") (name "/J800_109") (class "Default")
      (node (ref "J800") (pin "109") (pinfunction "IO_P_109") (pintype "passive"))
    )
    (net (code "238") (name "/J800_110") (class "Default")
      (node (ref "J800") (pin "110") (pinfunction "IO_N_110") (pintype "passive"))
    )
    (net (code "239") (name "/J800_111") (class "Default")
      (node (ref "J800") (pin "111") (pinfunction "IO_N_111") (pintype "passive"))
    )
    (net (code "240") (name "/J800_112") (class "Default")
      (node (ref "J800") (pin "112") (pinfunction "IO_P_112") (pintype "passive"))
    )
    (net (code "241") (name "/J800_114") (class "Default")
      (node (ref "J800") (pin "114") (pinfunction "IO_N_114") (pintype "passive"))
    )
    (net (code "242") (name "/J800_115") (class "Default")
      (node (ref "J800") (pin "115") (pinfunction "SCLK_P_115") (pintype "passive"))
    )
    (net (code "243") (name "/J800_116") (class "Default")
      (node (ref "J800") (pin "116") (pinfunction "VIN_IO_116") (pintype "passive"))
    )
    (net (code "244") (name "/J800_117") (class "Default")
      (node (ref "J800") (pin "117") (pinfunction "SCLK_N_117") (pintype "passive"))
    )
    (net (code "245") (name "/J800_118") (class "Default")
      (node (ref "J800") (pin "118") (pinfunction "IO_P_118") (pintype "passive"))
    )
    (net (code "246") (name "/J800_119") (class "Default")
      (node (ref "J800") (pin "119") (pinfunction "IO_P_119") (pintype "passive"))
    )
    (net (code "247") (name "/J800_120") (class "Default")
      (node (ref "J800") (pin "120") (pinfunction "IO_N_120") (pintype "passive"))
    )
    (net (code "248") (name "/J800_121") (class "Default")
      (node (ref "J800") (pin "121") (pinfunction "IO_N_121") (pintype "passive"))
    )
    (net (code "249") (name "/J800_122") (class "Default")
      (node (ref "J800") (pin "122") (pinfunction "SCLK_P_122") (pintype "passive"))
    )
    (net (code "250") (name "/J800_123") (class "Default")
      (node (ref "J800") (pin "123") (pinfunction "VOUT_123") (pintype "passive"))
    )
    (net (code "251") (name "/J800_124") (class "Default")
      (node (ref "J800") (pin "124") (pinfunction "SCLK_N_124") (pintype "passive"))
    )
    (net (code "252") (name "/J800_125") (class "Default")
      (node (ref "J800") (pin "125") (pinfunction "IO_P_125") (pintype "passive"))
    )
    (net (code "253") (name "/J800_127") (class "Default")
      (node (ref "J800") (pin "127") (pinfunction "IO_N_127") (pintype "passive"))
    )
    (net (code "254") (name "/J800_128") (class "Default")
      (node (ref "J800") (pin "128") (pinfunction "IO_P_128") (pintype "passive"))
    )
    (net (code "255") (name "/J800_129") (class "Default")
      (node (ref "J800") (pin "129") (pinfunction "IO_P_129") (pintype "passive"))
    )
    (net (code "256") (name "/J800_130") (class "Default")
      (node (ref "J800") (pin "130") (pinfunction "IO_N_130") (pintype "passive"))
    )
    (net (code "257") (name "/J800_131") (class "Default")
      (node (ref "J800") (pin "131") (pinfunction "IO_N_131") (pintype "passive"))
    )
    (net (code "258") (name "/J800_132") (class "Default")
      (node (ref "J800") (pin "132") (pinfunction "IO_P_132") (pintype "passive"))
    )
    (net (code "259") (name "/J800_134") (class "Default")
      (node (ref "J800") (pin "134") (pinfunction "IO_N_134") (pintype "passive"))
    )
    (net (code "260") (name "/J800_135") (class "Default")
      (node (ref "J800") (pin "135") (pinfunction "IO_P_135") (pintype "passive"))
    )
    (net (code "261") (name "/J800_136") (class "Default")
      (node (ref "J800") (pin "136") (pinfunction "VOUT_3V3_136") (pintype "passive"))
    )
    (net (code "262") (name "/J800_137") (class "Default")
      (node (ref "J800") (pin "137") (pinfunction "IO_N_137") (pintype "passive"))
    )
    (net (code "263") (name "/J800_138") (class "Default")
      (node (ref "J800") (pin "138") (pinfunction "IO_P_138") (pintype "passive"))
    )
    (net (code "264") (name "/J800_139") (class "Default")
      (node (ref "J800") (pin "139") (pinfunction "IO_P_139") (pintype "passive"))
    )
    (net (code "265") (name "/J800_140") (class "Default")
      (node (ref "J800") (pin "140") (pinfunction "IO_N_140") (pintype "passive"))
    )
    (net (code "266") (name "/J800_141") (class "Default")
      (node (ref "J800") (pin "141") (pinfunction "IO_N_141") (pintype "passive"))
    )
    (net (code "267") (name "/J800_142") (class "Default")
      (node (ref "J800") (pin "142") (pinfunction "IO_P_142") (pintype "passive"))
    )
    (net (code "268") (name "/J800_143") (class "Default")
      (node (ref "J800") (pin "143") (pinfunction "VOUT_3V3_143") (pintype "passive"))
    )
    (net (code "269") (name "/J800_144") (class "Default")
      (node (ref "J800") (pin "144") (pinfunction "IO_N_144") (pintype "passive"))
    )
    (net (code "270") (name "/J800_145") (class "Default")
      (node (ref "J800") (pin "145") (pinfunction "IO_P_145") (pintype "passive"))
    )
    (net (code "271") (name "/J800_147") (class "Default")
      (node (ref "J800") (pin "147") (pinfunction "IO_N_147") (pintype "passive"))
    )
    (net (code "272") (name "/J800_148") (class "Default")
      (node (ref "J800") (pin "148") (pinfunction "PCLK_P_148") (pintype "passive"))
    )
    (net (code "273") (name "/J800_150") (class "Default")
      (node (ref "J800") (pin "150") (pinfunction "PCLK_N_150") (pintype "passive"))
    )
    (net (code "274") (name "/J800_151") (class "Default")
      (node (ref "J800") (pin "151") (pinfunction "SCLK_P_151") (pintype "passive"))
    )
    (net (code "275") (name "/J800_153") (class "Default")
      (node (ref "J800") (pin "153") (pinfunction "SCLK_N_153") (pintype "passive"))
    )
    (net (code "276") (name "/J800_154") (class "Default")
      (node (ref "J800") (pin "154") (pinfunction "IO_P_154") (pintype "passive"))
    )
    (net (code "277") (name "/J800_156") (class "Default")
      (node (ref "J800") (pin "156") (pinfunction "IO_N_156") (pintype "passive"))
    )
    (net (code "278") (name "/J800_157") (class "Default")
      (node (ref "J800") (pin "157") (pinfunction "IO_P_157") (pintype "passive"))
    )
    (net (code "279") (name "/J800_158") (class "Default")
      (node (ref "J800") (pin "158") (pinfunction "VIN_IO_158") (pintype "passive"))
    )
    (net (code "280") (name "/J800_159") (class "Default")
      (node (ref "J800") (pin "159") (pinfunction "IO_N_159") (pintype "passive"))
    )
    (net (code "281") (name "/J800_160") (class "Default")
      (node (ref "J800") (pin "160") (pinfunction "IO_P_160") (pintype "passive"))
    )
    (net (code "282") (name "/J800_161") (class "Default")
      (node (ref "J800") (pin "161") (pinfunction "IO_P_161") (pintype "passive"))
    )
    (net (code "283") (name "/J800_162") (class "Default")
      (node (ref "J800") (pin "162") (pinfunction "IO_N_162") (pintype "passive"))
    )
    (net (code "284") (name "/J800_163") (class "Default")
      (node (ref "J800") (pin "163") (pinfunction "IO_N_163") (pintype "passive"))
    )
    (net (code "285") (name "/J800_164") (class "Default")
      (node (ref "J800") (pin "164") (pinfunction "IO_P_164") (pintype "passive"))
    )
    (net (code "286") (name "/J800_165") (class "Default")
      (node (ref "J800") (pin "165") (pinfunction "VOUT_165") (pintype "passive"))
    )
    (net (code "287") (name "/J800_166") (class "Default")
      (node (ref "J800") (pin "166") (pinfunction "IO_N_166") (pintype "passive"))
    )
    (net (code "288") (name "/J800_167") (class "Default")
      (node (ref "J800") (pin "167") (pinfunction "RSVD_167") (pintype "passive"))
    )
    (net (code "289") (name "/JTAG_TCK") (class "Default")
      (node (ref "J700") (pin "123") (pinfunction "JTAG_TCK_123") (pintype "passive"))
    )
    (net (code "290") (name "/JTAG_TDI") (class "Default")
      (node (ref "J700") (pin "117") (pinfunction "JTAG_TDI_117") (pintype "passive"))
    )
    (net (code "291") (name "/JTAG_TDO") (class "Default")
      (node (ref "J700") (pin "121") (pinfunction "JTAG_TDO_121") (pintype "passive"))
    )
    (net (code "292") (name "/JTAG_TMS") (class "Default")
      (node (ref "J700") (pin "119") (pinfunction "JTAG_TMS_119") (pintype "passive"))
    )
    (net (code "293") (name "/MGT_CLK_1_N") (class "Default")
      (node (ref "J701") (pin "6") (pinfunction "MGT_CLK_N_6") (pintype "passive"))
    )
    (net (code "294") (name "/MGT_CLK_1_P") (class "Default")
      (node (ref "J701") (pin "4") (pinfunction "MGT_CLK_P_4") (pintype "passive"))
    )
    (net (code "295") (name "/MGT_CLK_2_N") (class "Default")
      (node (ref "J701") (pin "12") (pinfunction "MGT_CLK_N_12") (pintype "passive"))
    )
    (net (code "296") (name "/MGT_CLK_2_P") (class "Default")
      (node (ref "J701") (pin "10") (pinfunction "MGT_CLK_P_10") (pintype "passive"))
    )
    (net (code "297") (name "/MGT_RX0_N") (class "Default")
      (node (ref "J701") (pin "20") (pinfunction "MGT_RX_N_20") (pintype "passive"))
    )
    (net (code "298") (name "/MGT_RX0_P") (class "Default")
      (node (ref "J701") (pin "16") (pinfunction "MGT_RX_P_16") (pintype "passive"))
    )
    (net (code "299") (name "/MGT_RX1_N") (class "Default")
      (node (ref "J701") (pin "28") (pinfunction "MGT_RX_N_28") (pintype "passive"))
    )
    (net (code "300") (name "/MGT_RX1_P") (class "Default")
      (node (ref "J701") (pin "24") (pinfunction "MGT_RX_P_24") (pintype "passive"))
    )
    (net (code "301") (name "/MGT_RX2_N") (class "Default")
      (node (ref "J701") (pin "36") (pinfunction "MGT_RX_N_36") (pintype "passive"))
    )
    (net (code "302") (name "/MGT_RX2_P") (class "Default")
      (node (ref "J701") (pin "32") (pinfunction "MGT_RX_P_32") (pintype "passive"))
    )
    (net (code "303") (name "/MGT_RX3_N") (class "Default")
      (node (ref "J701") (pin "44") (pinfunction "MGT_RX_N_44") (pintype "passive"))
    )
    (net (code "304") (name "/MGT_RX3_P") (class "Default")
      (node (ref "J701") (pin "40") (pinfunction "MGT_RX_P_40") (pintype "passive"))
    )
    (net (code "305") (name "/MGT_TX0_N") (class "Default")
      (node (ref "J701") (pin "17") (pinfunction "MGT_TX_N_17") (pintype "passive"))
    )
    (net (code "306") (name "/MGT_TX0_P") (class "Default")
      (node (ref "J701") (pin "13") (pinfunction "MGT_TX_P_13") (pintype "passive"))
    )
    (net (code "307") (name "/MGT_TX1_N") (class "Default")
      (node (ref "J701") (pin "25") (pinfunction "MGT_TX_N_25") (pintype "passive"))
    )
    (net (code "308") (name "/MGT_TX1_P") (class "Default")
      (node (ref "J701") (pin "21") (pinfunction "MGT_TX_P_21") (pintype "passive"))
    )
    (net (code "309") (name "/MGT_TX2_N") (class "Default")
      (node (ref "J701") (pin "33") (pinfunction "MGT_TX_N_33") (pintype "passive"))
    )
    (net (code "310") (name "/MGT_TX2_P") (class "Default")
      (node (ref "J701") (pin "29") (pinfunction "MGT_TX_P_29") (pintype "passive"))
    )
    (net (code "311") (name "/MGT_TX3_N") (class "Default")
      (node (ref "J701") (pin "41") (pinfunction "MGT_TX_N_41") (pintype "passive"))
    )
    (net (code "312") (name "/MGT_TX3_P") (class "Default")
      (node (ref "J701") (pin "37") (pinfunction "MGT_TX_P_37") (pintype "passive"))
    )
    (net (code "313") (name "/SCLK") (class "Default")
      (node (ref "J700") (pin "17") (pinfunction "IO_N_17") (pintype "passive"))
    )
    (net (code "314") (name "/SCLK{slash}MGT_RCLK_N") (class "Default")
      (node (ref "J701") (pin "5") (pinfunction "SCLK_N_5") (pintype "passive"))
    )
    (net (code "315") (name "/SCLK{slash}MGT_RCLK_P") (class "Default")
      (node (ref "J701") (pin "3") (pinfunction "SCLK_P_3") (pintype "passive"))
    )
    (net (code "316") (name "/SDIO") (class "Default")
      (node (ref "J700") (pin "15") (pinfunction "IO_P_15") (pintype "passive"))
    )
    (net (code "317") (name "/SDO") (class "Default")
      (node (ref "J700") (pin "69") (pinfunction "IO_N_69") (pintype "passive"))
    )
    (net (code "318") (name "DGND") (class "Default")
      (node (ref "J700") (pin "108") (pinfunction "GND_108") (pintype "power_in"))
      (node (ref "J700") (pin "109") (pinfunction "GND_109") (pintype "power_in"))
      (node (ref "J700") (pin "120") (pinfunction "GND_120") (pintype "power_in"))
      (node (ref "J700") (pin "125") (pinfunction "GND_125") (pintype "power_in"))
      (node (ref "J700") (pin "13") (pinfunction "GND_13") (pintype "power_in"))
      (node (ref "J700") (pin "134") (pinfunction "GND_134") (pintype "power_in"))
      (node (ref "J700") (pin "135") (pinfunction "GND_135") (pintype "power_in"))
      (node (ref "J700") (pin "138") (pinfunction "GND_138") (pintype "power_in"))
      (node (ref "J700") (pin "139") (pinfunction "GND_139") (pintype "power_in"))
      (node (ref "J700") (pin "14") (pinfunction "GND_14") (pintype "power_in"))
      (node (ref "J700") (pin "142") (pinfunction "GND_142") (pintype "power_in"))
      (node (ref "J700") (pin "143") (pinfunction "GND_143") (pintype "power_in"))
      (node (ref "J700") (pin "166") (pinfunction "GND_166") (pintype "power_in"))
      (node (ref "J700") (pin "167") (pinfunction "GND_167") (pintype "power_in"))
      (node (ref "J700") (pin "20") (pinfunction "GND_20") (pintype "power_in"))
      (node (ref "J700") (pin "23") (pinfunction "GND_23") (pintype "power_in"))
      (node (ref "J700") (pin "32") (pinfunction "GND_32") (pintype "power_in"))
      (node (ref "J700") (pin "35") (pinfunction "GND_35") (pintype "power_in"))
      (node (ref "J700") (pin "44") (pinfunction "GND_44") (pintype "power_in"))
      (node (ref "J700") (pin "47") (pinfunction "GND_47") (pintype "power_in"))
      (node (ref "J700") (pin "56") (pinfunction "GND_56") (pintype "power_in"))
      (node (ref "J700") (pin "59") (pinfunction "GND_59") (pintype "power_in"))
      (node (ref "J700") (pin "65") (pinfunction "VOUT_65") (pintype "power_in"))
      (node (ref "J700") (pin "68") (pinfunction "GND_68") (pintype "power_in"))
      (node (ref "J700") (pin "71") (pinfunction "GND_71") (pintype "power_in"))
      (node (ref "J700") (pin "80") (pinfunction "GND_80") (pintype "power_in"))
      (node (ref "J700") (pin "83") (pinfunction "GND_83") (pintype "power_in"))
      (node (ref "J700") (pin "96") (pinfunction "GND_96") (pintype "power_in"))
      (node (ref "J700") (pin "99") (pinfunction "GND_99") (pintype "power_in"))
      (node (ref "J701") (pin "1") (pinfunction "GND_1") (pintype "passive"))
      (node (ref "J701") (pin "105") (pinfunction "GND_105") (pintype "passive"))
      (node (ref "J701") (pin "11") (pinfunction "GND_11") (pintype "passive"))
      (node (ref "J701") (pin "118") (pinfunction "GND_118") (pintype "passive"))
      (node (ref "J701") (pin "121") (pinfunction "GND_121") (pintype "passive"))
      (node (ref "J701") (pin "134") (pinfunction "GND_134") (pintype "passive"))
      (node (ref "J701") (pin "137") (pinfunction "GND_137") (pintype "passive"))
      (node (ref "J701") (pin "14") (pinfunction "GND_14") (pintype "passive"))
      (node (ref "J701") (pin "146") (pinfunction "GND_146") (pintype "passive"))
      (node (ref "J701") (pin "149") (pinfunction "GND_149") (pintype "passive"))
      (node (ref "J701") (pin "15") (pinfunction "GND_15") (pintype "passive"))
      (node (ref "J701") (pin "161") (pinfunction "GND_161") (pintype "passive"))
      (node (ref "J701") (pin "18") (pinfunction "GND_18") (pintype "passive"))
      (node (ref "J701") (pin "19") (pinfunction "GND_19") (pintype "passive"))
      (node (ref "J701") (pin "2") (pinfunction "GND_2") (pintype "passive"))
      (node (ref "J701") (pin "22") (pinfunction "GND_22") (pintype "passive"))
      (node (ref "J701") (pin "23") (pinfunction "GND_23") (pintype "passive"))
      (node (ref "J701") (pin "26") (pinfunction "GND_26") (pintype "passive"))
      (node (ref "J701") (pin "27") (pinfunction "GND_27") (pintype "passive"))
      (node (ref "J701") (pin "30") (pinfunction "GND_30") (pintype "passive"))
      (node (ref "J701") (pin "31") (pinfunction "GND_31") (pintype "passive"))
      (node (ref "J701") (pin "34") (pinfunction "GND_34") (pintype "passive"))
      (node (ref "J701") (pin "35") (pinfunction "GND_35") (pintype "passive"))
      (node (ref "J701") (pin "38") (pinfunction "GND_38") (pintype "passive"))
      (node (ref "J701") (pin "39") (pinfunction "GND_39") (pintype "passive"))
      (node (ref "J701") (pin "42") (pinfunction "GND_42") (pintype "passive"))
      (node (ref "J701") (pin "43") (pinfunction "GND_43") (pintype "passive"))
      (node (ref "J701") (pin "46") (pinfunction "GND_46") (pintype "passive"))
      (node (ref "J701") (pin "49") (pinfunction "GND_49") (pintype "passive"))
      (node (ref "J701") (pin "58") (pinfunction "GND_58") (pintype "passive"))
      (node (ref "J701") (pin "61") (pinfunction "GND_61") (pintype "passive"))
      (node (ref "J701") (pin "70") (pinfunction "GND_70") (pintype "passive"))
      (node (ref "J701") (pin "73") (pinfunction "GND_73") (pintype "passive"))
      (node (ref "J701") (pin "82") (pinfunction "GND_82") (pintype "passive"))
      (node (ref "J701") (pin "85") (pinfunction "GND_85") (pintype "passive"))
      (node (ref "J701") (pin "98") (pinfunction "GND_98") (pintype "passive"))
      (node (ref "J800") (pin "1") (pinfunction "GND_1") (pintype "passive"))
      (node (ref "J800") (pin "106") (pinfunction "GND_106") (pintype "passive"))
      (node (ref "J800") (pin "11") (pinfunction "GND_11") (pintype "passive"))
      (node (ref "J800") (pin "113") (pinfunction "GND_113") (pintype "passive"))
      (node (ref "J800") (pin "126") (pinfunction "GND_126") (pintype "passive"))
      (node (ref "J800") (pin "133") (pinfunction "GND_133") (pintype "passive"))
      (node (ref "J800") (pin "14") (pinfunction "GND_14") (pintype "passive"))
      (node (ref "J800") (pin "146") (pinfunction "GND_146") (pintype "passive"))
      (node (ref "J800") (pin "149") (pinfunction "GND_149") (pintype "passive"))
      (node (ref "J800") (pin "15") (pinfunction "GND_15") (pintype "passive"))
      (node (ref "J800") (pin "152") (pinfunction "GND_152") (pintype "passive"))
      (node (ref "J800") (pin "155") (pinfunction "GND_155") (pintype "passive"))
      (node (ref "J800") (pin "168") (pinfunction "GND_168") (pintype "passive"))
      (node (ref "J800") (pin "18") (pinfunction "GND_18") (pintype "passive"))
      (node (ref "J800") (pin "19") (pinfunction "GND_19") (pintype "passive"))
      (node (ref "J800") (pin "2") (pinfunction "GND_2") (pintype "passive"))
      (node (ref "J800") (pin "22") (pinfunction "GND_22") (pintype "passive"))
      (node (ref "J800") (pin "23") (pinfunction "GND_23") (pintype "passive"))
      (node (ref "J800") (pin "26") (pinfunction "GND_26") (pintype "passive"))
      (node (ref "J800") (pin "27") (pinfunction "GND_27") (pintype "passive"))
      (node (ref "J800") (pin "30") (pinfunction "GND_30") (pintype "passive"))
      (node (ref "J800") (pin "31") (pinfunction "GND_31") (pintype "passive"))
      (node (ref "J800") (pin "34") (pinfunction "GND_34") (pintype "passive"))
      (node (ref "J800") (pin "35") (pinfunction "GND_35") (pintype "passive"))
      (node (ref "J800") (pin "38") (pinfunction "GND_38") (pintype "passive"))
      (node (ref "J800") (pin "39") (pinfunction "GND_39") (pintype "passive"))
      (node (ref "J800") (pin "42") (pinfunction "GND_42") (pintype "passive"))
      (node (ref "J800") (pin "43") (pinfunction "GND_43") (pintype "passive"))
      (node (ref "J800") (pin "46") (pinfunction "GND_46") (pintype "passive"))
      (node (ref "J800") (pin "49") (pinfunction "GND_49") (pintype "passive"))
      (node (ref "J800") (pin "52") (pinfunction "GND_52") (pintype "passive"))
      (node (ref "J800") (pin "55") (pinfunction "GND_55") (pintype "passive"))
      (node (ref "J800") (pin "58") (pinfunction "GND_58") (pintype "passive"))
      (node (ref "J800") (pin "61") (pinfunction "GND_61") (pintype "passive"))
      (node (ref "J800") (pin "64") (pinfunction "GND_64") (pintype "passive"))
      (node (ref "J800") (pin "67") (pinfunction "GND_67") (pintype "passive"))
      (node (ref "J800") (pin "70") (pinfunction "GND_70") (pintype "passive"))
      (node (ref "J800") (pin "73") (pinfunction "GND_73") (pintype "passive"))
      (node (ref "J800") (pin "86") (pinfunction "GND_86") (pintype "passive"))
      (node (ref "J800") (pin "93") (pinfunction "GND_93") (pintype "passive"))
    )
    (net (code "319") (name "DVDD25") (class "Default")
      (node (ref "J700") (pin "38") (pinfunction "VIN_IO_38") (pintype "power_in"))
      (node (ref "J700") (pin "74") (pinfunction "VIN_CFG_74") (pintype "power_in"))
      (node (ref "J701") (pin "140") (pinfunction "VIN_IO_140") (pintype "passive"))
      (node (ref "J701") (pin "143") (pinfunction "VIN_IO_143") (pintype "passive"))
      (node (ref "J701") (pin "64") (pinfunction "VIN_IO_64") (pintype "passive"))
      (node (ref "J701") (pin "67") (pinfunction "VIN_IO_67") (pintype "passive"))
      (node (ref "J701") (pin "88") (pinfunction "VIN_IO_88") (pintype "passive"))
      (node (ref "J701") (pin "95") (pinfunction "VIN_IO_95") (pintype "passive"))
    )
    (net (code "320") (name "DVDD33") (class "Default")
      (node (ref "J700") (pin "10") (pinfunction "PWR_EN_10") (pintype "passive"))
    )
    (net (code "321") (name "OVDD18") (class "Default")
      (node (ref "J700") (pin "41") (pinfunction "VIN_IO_41") (pintype "power_in"))
      (node (ref "J700") (pin "77") (pinfunction "VIN_CFG_77") (pintype "power_in"))
    )
    (net (code "322") (name "unconnected-(J700-BOOT_MODE-Pad126)") (class "Default")
      (node (ref "J700") (pin "126") (pinfunction "BOOT_MODE_126") (pintype "passive"))
    )
    (net (code "323") (name "unconnected-(J700-ETH_CTREF-Pad154)") (class "Default")
      (node (ref "J700") (pin "154") (pinfunction "ETH_CTREF_154") (pintype "passive"))
    )
    (net (code "324") (name "unconnected-(J700-ETH_CTREF-Pad155)") (class "Default")
      (node (ref "J700") (pin "155") (pinfunction "ETH_CTREF_155") (pintype "passive"))
    )
    (net (code "325") (name "unconnected-(J700-ETH_LED1#-Pad148)") (class "Default")
      (node (ref "J700") (pin "148") (pinfunction "ETH_LED1#_148") (pintype "passive"))
    )
    (net (code "326") (name "unconnected-(J700-ETH_LED1#-Pad149)") (class "Default")
      (node (ref "J700") (pin "149") (pinfunction "ETH_LED1#_149") (pintype "passive"))
    )
    (net (code "327") (name "unconnected-(J700-ETH_LED2#-Pad160)") (class "Default")
      (node (ref "J700") (pin "160") (pinfunction "ETH_LED2#_160") (pintype "passive"))
    )
    (net (code "328") (name "unconnected-(J700-ETH_LED2#-Pad161)") (class "Default")
      (node (ref "J700") (pin "161") (pinfunction "ETH_LED2#_161") (pintype "passive"))
    )
    (net (code "329") (name "unconnected-(J700-FLASH_CLK-Pad118)") (class "Default")
      (node (ref "J700") (pin "118") (pinfunction "FLASH_CLK_118") (pintype "passive"))
    )
    (net (code "330") (name "unconnected-(J700-FLASH_CS#-Pad116)") (class "Default")
      (node (ref "J700") (pin "116") (pinfunction "FLASH_CS#_116") (pintype "passive"))
    )
    (net (code "331") (name "unconnected-(J700-FLASH_DI-Pad114)") (class "Default")
      (node (ref "J700") (pin "114") (pinfunction "FLASH_DI_114") (pintype "passive"))
    )
    (net (code "332") (name "unconnected-(J700-FLASH_DO-Pad122)") (class "Default")
      (node (ref "J700") (pin "122") (pinfunction "FLASH_DO_122") (pintype "passive"))
    )
    (net (code "333") (name "unconnected-(J700-FPGA_DONE-Pad130)") (class "Default")
      (node (ref "J700") (pin "130") (pinfunction "FPGA_DONE_130") (pintype "passive"))
    )
    (net (code "334") (name "unconnected-(J700-ID_HDM-Pad133)") (class "Default")
      (node (ref "J700") (pin "133") (pinfunction "ID_HDM_133") (pintype "passive"))
    )
    (net (code "335") (name "unconnected-(J700-IO_N-Pad24)") (class "Default")
      (node (ref "J700") (pin "24") (pinfunction "IO_N_24") (pintype "passive"))
    )
    (net (code "336") (name "unconnected-(J700-IO_N-Pad30)") (class "Default")
      (node (ref "J700") (pin "30") (pinfunction "IO_N_30") (pintype "passive"))
    )
    (net (code "337") (name "unconnected-(J700-IO_N-Pad84)") (class "Default")
      (node (ref "J700") (pin "84") (pinfunction "IO_N_84") (pintype "passive"))
    )
    (net (code "338") (name "unconnected-(J700-IO_P-Pad22)") (class "Default")
      (node (ref "J700") (pin "22") (pinfunction "IO_P_22") (pintype "passive"))
    )
    (net (code "339") (name "unconnected-(J700-IO_P-Pad28)") (class "Default")
      (node (ref "J700") (pin "28") (pinfunction "IO_P_28") (pintype "passive"))
    )
    (net (code "340") (name "unconnected-(J700-IO_P-Pad67)") (class "Default")
      (node (ref "J700") (pin "67") (pinfunction "IO_P_67") (pintype "passive"))
    )
    (net (code "341") (name "unconnected-(J700-IO_P-Pad82)") (class "Default")
      (node (ref "J700") (pin "82") (pinfunction "IO_P_82") (pintype "passive"))
    )
    (net (code "342") (name "unconnected-(J700-IO_P-Pad92)") (class "Default")
      (node (ref "J700") (pin "92") (pinfunction "IO_P_92") (pintype "passive"))
    )
    (net (code "343") (name "unconnected-(J700-PCLK_N-Pad87)") (class "Default")
      (node (ref "J700") (pin "87") (pinfunction "PCLK_N_87") (pintype "passive"))
    )
    (net (code "344") (name "unconnected-(J700-PCLK_P-Pad85)") (class "Default")
      (node (ref "J700") (pin "85") (pinfunction "PCLK_P_85") (pintype "passive"))
    )
    (net (code "345") (name "unconnected-(J700-POR#_LOAD#-Pad132)") (class "Default")
      (node (ref "J700") (pin "132") (pinfunction "POR#_LOAD#_132") (pintype "passive"))
    )
    (net (code "346") (name "unconnected-(J700-PWR_GOOD-Pad12)") (class "Default")
      (node (ref "J700") (pin "12") (pinfunction "PWR_GOOD_12") (pintype "passive"))
    )
    (net (code "347") (name "unconnected-(J700-RSVD-Pad110)") (class "Default")
      (node (ref "J700") (pin "110") (pinfunction "RSVD_110") (pintype "passive"))
    )
    (net (code "348") (name "unconnected-(J700-RSVD-Pad112)") (class "Default")
      (node (ref "J700") (pin "112") (pinfunction "RSVD_112") (pintype "passive"))
    )
    (net (code "349") (name "unconnected-(J700-SCLK_N-Pad18)") (class "Default")
      (node (ref "J700") (pin "18") (pinfunction "SCLK_N_18") (pintype "passive"))
    )
    (net (code "350") (name "unconnected-(J700-SCLK_P-Pad16)") (class "Default")
      (node (ref "J700") (pin "16") (pinfunction "SCLK_P_16") (pintype "passive"))
    )
    (net (code "351") (name "unconnected-(J700-SRST#_RDY#-Pad124)") (class "Default")
      (node (ref "J700") (pin "124") (pinfunction "SRST#_RDY#_124") (pintype "passive"))
    )
    (net (code "352") (name "unconnected-(J700-USB_CPEN-Pad128)") (class "Default")
      (node (ref "J700") (pin "128") (pinfunction "USB_CPEN_128") (pintype "passive"))
    )
    (net (code "353") (name "unconnected-(J700-USB_DM-Pad129)") (class "Default")
      (node (ref "J700") (pin "129") (pinfunction "USB_DM_129") (pintype "passive"))
    )
    (net (code "354") (name "unconnected-(J700-USB_DP-Pad127)") (class "Default")
      (node (ref "J700") (pin "127") (pinfunction "USB_DP_127") (pintype "passive"))
    )
    (net (code "355") (name "unconnected-(J700-USB_SSRX_N-Pad141)") (class "Default")
      (node (ref "J700") (pin "141") (pinfunction "USB_SSRX_N_141") (pintype "passive"))
    )
    (net (code "356") (name "unconnected-(J700-USB_SSRX_P-Pad137)") (class "Default")
      (node (ref "J700") (pin "137") (pinfunction "USB_SSRX_P_137") (pintype "passive"))
    )
    (net (code "357") (name "unconnected-(J700-USB_SSTX_N-Pad140)") (class "Default")
      (node (ref "J700") (pin "140") (pinfunction "USB_SSTX_N_140") (pintype "passive"))
    )
    (net (code "358") (name "unconnected-(J700-USB_SSTX_P-Pad136)") (class "Default")
      (node (ref "J700") (pin "136") (pinfunction "USB_SSTX_P_136") (pintype "passive"))
    )
    (net (code "359") (name "unconnected-(J700-VBUS_HDP-Pad131)") (class "Default")
      (node (ref "J700") (pin "131") (pinfunction "VBUS_HDP_131") (pintype "passive"))
    )
    (net (code "360") (name "unconnected-(J700-VIN_BAT-Pad168)") (class "Default")
      (node (ref "J700") (pin "168") (pinfunction "VIN_BAT_168") (pintype "power_in"))
    )
    (net (code "361") (name "unconnected-(J700-VIN_MOD-Pad1)") (class "Default")
      (node (ref "J700") (pin "1") (pinfunction "VIN_MOD_1") (pintype "power_in"))
    )
    (net (code "362") (name "unconnected-(J700-VIN_MOD-Pad2)") (class "Default")
      (node (ref "J700") (pin "2") (pinfunction "VIN_MOD_2") (pintype "power_in"))
    )
    (net (code "363") (name "unconnected-(J700-VIN_MOD-Pad3)") (class "Default")
      (node (ref "J700") (pin "3") (pinfunction "VIN_MOD_3") (pintype "power_in"))
    )
    (net (code "364") (name "unconnected-(J700-VIN_MOD-Pad4)") (class "Default")
      (node (ref "J700") (pin "4") (pinfunction "VIN_MOD_4") (pintype "power_in"))
    )
    (net (code "365") (name "unconnected-(J700-VIN_MOD-Pad5)") (class "Default")
      (node (ref "J700") (pin "5") (pinfunction "VIN_MOD_5") (pintype "power_in"))
    )
    (net (code "366") (name "unconnected-(J700-VIN_MOD-Pad6)") (class "Default")
      (node (ref "J700") (pin "6") (pinfunction "VIN_MOD_6") (pintype "power_in"))
    )
    (net (code "367") (name "unconnected-(J700-VIN_MOD-Pad7)") (class "Default")
      (node (ref "J700") (pin "7") (pinfunction "VIN_MOD_7") (pintype "power_in"))
    )
    (net (code "368") (name "unconnected-(J700-VIN_MOD-Pad8)") (class "Default")
      (node (ref "J700") (pin "8") (pinfunction "VIN_MOD_8") (pintype "power_in"))
    )
    (net (code "369") (name "unconnected-(J700-VIN_MOD-Pad9)") (class "Default")
      (node (ref "J700") (pin "9") (pinfunction "VIN_MOD_9") (pintype "power_in"))
    )
    (net (code "370") (name "unconnected-(J700-VIN_MOD-Pad11)") (class "Default")
      (node (ref "J700") (pin "11") (pinfunction "VIN_MOD_11") (pintype "power_in"))
    )
    (net (code "371") (name "unconnected-(J700-VMON-Pad102)") (class "Default")
      (node (ref "J700") (pin "102") (pinfunction "VMON_102") (pintype "passive"))
    )
    (net (code "372") (name "unconnected-(J700-VOUT-Pad53)") (class "Default")
      (node (ref "J700") (pin "53") (pinfunction "VOUT_53") (pintype "power_in"))
    )
    (net (code "373") (name "unconnected-(J700-VOUT-Pad62)") (class "Default")
      (node (ref "J700") (pin "62") (pinfunction "VOUT_62") (pintype "power_in"))
    )
    (net (code "374") (name "unconnected-(J700-VOUT-Pad89)") (class "Default")
      (node (ref "J700") (pin "89") (pinfunction "VOUT_89") (pintype "power_in"))
    )
    (net (code "375") (name "unconnected-(J700-VOUT_3V3-Pad26)") (class "Default")
      (node (ref "J700") (pin "26") (pinfunction "VOUT_3V3_26") (pintype "power_in"))
    )
    (net (code "376") (name "unconnected-(J700-VOUT_3V3-Pad29)") (class "Default")
      (node (ref "J700") (pin "29") (pinfunction "VOUT_3V3_29") (pintype "power_in"))
    )
    (net (code "377") (name "unconnected-(J700-VOUT_3V3-Pad50)") (class "Default")
      (node (ref "J700") (pin "50") (pinfunction "VOUT_3V3_50") (pintype "power_in"))
    )
    (net (code "378") (name "unconnected-(J700-VOUT_3V3-Pad86)") (class "Default")
      (node (ref "J700") (pin "86") (pinfunction "VOUT_3V3_86") (pintype "power_in"))
    )
    (net (code "379") (name "unconnected-(J701-GND-Pad158)") (class "Default")
      (node (ref "J701") (pin "158") (pinfunction "GND_158") (pintype "passive"))
    )
    (net (code "380") (name "unconnected-(J701-VMON-Pad8)") (class "Default")
      (node (ref "J701") (pin "8") (pinfunction "VMON_8") (pintype "passive"))
    )
    (net (code "381") (name "unconnected-(J701-VMON-Pad167)") (class "Default")
      (node (ref "J701") (pin "167") (pinfunction "VMON_167") (pintype "passive"))
    )
    (net (code "382") (name "unconnected-(J701-VMON-Pad168)") (class "Default")
      (node (ref "J701") (pin "168") (pinfunction "VMON_168") (pintype "passive"))
    )
    (net (code "383") (name "unconnected-(J701-VOUT-Pad52)") (class "Default")
      (node (ref "J701") (pin "52") (pinfunction "VOUT_52") (pintype "passive"))
    )
    (net (code "384") (name "unconnected-(J701-VOUT-Pad76)") (class "Default")
      (node (ref "J701") (pin "76") (pinfunction "VOUT_76") (pintype "passive"))
    )
    (net (code "385") (name "unconnected-(J701-VOUT-Pad108)") (class "Default")
      (node (ref "J701") (pin "108") (pinfunction "VOUT_108") (pintype "passive"))
    )
    (net (code "386") (name "unconnected-(J701-VOUT-Pad128)") (class "Default")
      (node (ref "J701") (pin "128") (pinfunction "VOUT_128") (pintype "passive"))
    )
    (net (code "387") (name "unconnected-(J701-VOUT_3V3-Pad55)") (class "Default")
      (node (ref "J701") (pin "55") (pinfunction "VOUT_3V3_55") (pintype "passive"))
    )
    (net (code "388") (name "unconnected-(J701-VOUT_3V3-Pad79)") (class "Default")
      (node (ref "J701") (pin "79") (pinfunction "VOUT_3V3_79") (pintype "passive"))
    )
    (net (code "389") (name "unconnected-(J701-VOUT_3V3-Pad115)") (class "Default")
      (node (ref "J701") (pin "115") (pinfunction "VOUT_3V3_115") (pintype "passive"))
    )
    (net (code "390") (name "unconnected-(J701-VOUT_3V3-Pad127)") (class "Default")
      (node (ref "J701") (pin "127") (pinfunction "VOUT_3V3_127") (pintype "passive"))
    )
    (net (code "391") (name "unconnected-(J701-VOUT_3V3-Pad152)") (class "Default")
      (node (ref "J701") (pin "152") (pinfunction "VOUT_3V3_152") (pintype "passive"))
    )
    (net (code "392") (name "unconnected-(J701-VOUT_3V3-Pad155)") (class "Default")
      (node (ref "J701") (pin "155") (pinfunction "VOUT_3V3_155") (pintype "passive"))
    )
  )
)
